# RELAY.net
KiCad netlist of a schematic drawn in Altium Designer
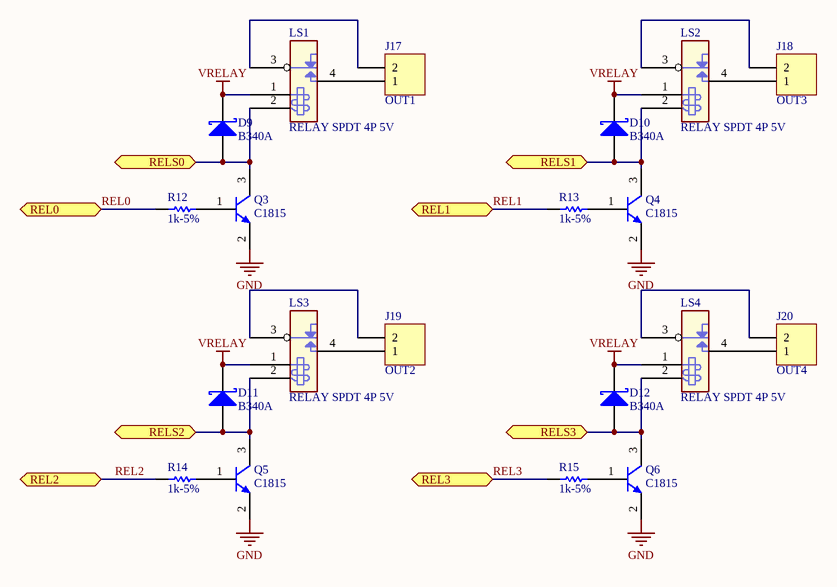
[diagram p0: RELAY.SchDoc]

(export (version "E")
  (design (tool "Eeschema 10.0.6"))
  (components
    (comp (ref "D9")
      (value "B340A")
      (footprint "DO_213AA")
      (description "DIODE SCHOTTKY 40V 3A SMA")
      (fields
        (field (name "DIGI-KEY PART NUMBER") "B340A-E3/61TGITR-ND")
        (field (name "MANUFACTURER PART NUMBER") "B340A-E3/61T")
        (field (name "PUBLISHER") "Altium Limited")
      )
      (libsource (lib "RobotClub") (part "D Schottky"))
    )
    (comp (ref "D10")
      (value "B340A")
      (footprint "DO_213AA")
      (description "DIODE SCHOTTKY 40V 3A SMA")
      (fields
        (field (name "DIGI-KEY PART NUMBER") "B340A-E3/61TGITR-ND")
        (field (name "MANUFACTURER PART NUMBER") "B340A-E3/61T")
        (field (name "PUBLISHER") "Altium Limited")
      )
      (libsource (lib "RobotClub") (part "D Schottky"))
    )
    (comp (ref "D11")
      (value "B340A")
      (footprint "DO_213AA")
      (description "DIODE SCHOTTKY 40V 3A SMA")
      (fields
        (field (name "DIGI-KEY PART NUMBER") "B340A-E3/61TGITR-ND")
        (field (name "MANUFACTURER PART NUMBER") "B340A-E3/61T")
        (field (name "PUBLISHER") "Altium Limited")
      )
      (libsource (lib "RobotClub") (part "D Schottky"))
    )
    (comp (ref "D12")
      (value "B340A")
      (footprint "DO_213AA")
      (description "DIODE SCHOTTKY 40V 3A SMA")
      (fields
        (field (name "DIGI-KEY PART NUMBER") "B340A-E3/61TGITR-ND")
        (field (name "MANUFACTURER PART NUMBER") "B340A-E3/61T")
        (field (name "PUBLISHER") "Altium Limited")
      )
      (libsource (lib "RobotClub") (part "D Schottky"))
    )
    (comp (ref "J17")
      (value "OUT1")
      (footprint "DOMINO NORMAL 2")
      (description "Header, 2-Pin")
      (fields (field (name "PUBLISHER") "Altium Limited"))
      (libsource (lib "RobotClub") (part "Header 2"))
    )
    (comp (ref "J18")
      (value "OUT3")
      (footprint "DOMINO NORMAL 2")
      (description "Header, 2-Pin")
      (fields (field (name "PUBLISHER") "Altium Limited"))
      (libsource (lib "RobotClub") (part "Header 2"))
    )
    (comp (ref "J19")
      (value "OUT2")
      (footprint "DOMINO NORMAL 2")
      (description "Header, 2-Pin")
      (fields (field (name "PUBLISHER") "Altium Limited"))
      (libsource (lib "RobotClub") (part "Header 2"))
    )
    (comp (ref "J20")
      (value "OUT4")
      (footprint "DOMINO NORMAL 2")
      (description "Header, 2-Pin")
      (fields (field (name "PUBLISHER") "Altium Limited"))
      (libsource (lib "RobotClub") (part "Header 2"))
    )
    (comp (ref "LS1")
      (value "RELAY SPDT 4P 5V")
      (footprint "RELAY_4PIN_5A_12")
      (libsource (lib "RobotClub") (part "RELAY SPDT 4P 5V"))
    )
    (comp (ref "LS2")
      (value "RELAY SPDT 4P 5V")
      (footprint "RELAY_4PIN_5A_12")
      (libsource (lib "RobotClub") (part "RELAY SPDT 4P 5V"))
    )
    (comp (ref "LS3")
      (value "RELAY SPDT 4P 5V")
      (footprint "RELAY_4PIN_5A_12")
      (libsource (lib "RobotClub") (part "RELAY SPDT 4P 5V"))
    )
    (comp (ref "LS4")
      (value "RELAY SPDT 4P 5V")
      (footprint "RELAY_4PIN_5A_12")
      (libsource (lib "RobotClub") (part "RELAY SPDT 4P 5V"))
    )
    (comp (ref "Q3")
      (value "C1815")
      (footprint "SOT-23B_N")
      (description "TRANSISTOR NPN 50V 150MA")
      (fields (field (name "DIGI-KEY PART NUMBER") "NA"))
      (libsource (lib "RobotClub") (part "NPN BEC"))
    )
    (comp (ref "Q4")
      (value "C1815")
      (footprint "SOT-23B_N")
      (description "TRANSISTOR NPN 50V 150MA")
      (fields (field (name "DIGI-KEY PART NUMBER") "NA"))
      (libsource (lib "RobotClub") (part "NPN BEC"))
    )
    (comp (ref "Q5")
      (value "C1815")
      (footprint "SOT-23B_N")
      (description "TRANSISTOR NPN 50V 150MA")
      (fields (field (name "DIGI-KEY PART NUMBER") "NA"))
      (libsource (lib "RobotClub") (part "NPN BEC"))
    )
    (comp (ref "Q6")
      (value "C1815")
      (footprint "SOT-23B_N")
      (description "TRANSISTOR NPN 50V 150MA")
      (fields (field (name "DIGI-KEY PART NUMBER") "NA"))
      (libsource (lib "RobotClub") (part "NPN BEC"))
    )
    (comp (ref "R12")
      (value "1k-5%")
      (footprint "R0603")
      (description "Resistor SMD 5%")
      (fields
        (field (name "DIGI-KEY PART NUMBER") "P3.24KLTR-ND")
        (field (name "MANUFACTURER") "Panasonic Electronic Components")
        (field (name "PUBLISHER") "Altium Limited")
      )
      (libsource (lib "RobotClub") (part "R_SMD5"))
    )
    (comp (ref "R13")
      (value "1k-5%")
      (footprint "R0603")
      (description "Resistor SMD 5%")
      (fields
        (field (name "DIGI-KEY PART NUMBER") "P3.24KLTR-ND")
        (field (name "MANUFACTURER") "Panasonic Electronic Components")
        (field (name "PUBLISHER") "Altium Limited")
      )
      (libsource (lib "RobotClub") (part "R_SMD5"))
    )
    (comp (ref "R14")
      (value "1k-5%")
      (footprint "R0603")
      (description "Resistor SMD 5%")
      (fields
        (field (name "DIGI-KEY PART NUMBER") "P3.24KLTR-ND")
        (field (name "MANUFACTURER") "Panasonic Electronic Components")
        (field (name "PUBLISHER") "Altium Limited")
      )
      (libsource (lib "RobotClub") (part "R_SMD5"))
    )
    (comp (ref "R15")
      (value "1k-5%")
      (footprint "R0603")
      (description "Resistor SMD 5%")
      (fields
        (field (name "DIGI-KEY PART NUMBER") "P3.24KLTR-ND")
        (field (name "MANUFACTURER") "Panasonic Electronic Components")
        (field (name "PUBLISHER") "Altium Limited")
      )
      (libsource (lib "RobotClub") (part "R_SMD5"))
    )
  )
  (nets
    (net (code "1") (name "/REL0") (class "Default")
      (node (ref "R12") (pin "1") (pinfunction "1_1") (pintype "passive"))
    )
    (net (code "2") (name "/REL1") (class "Default")
      (node (ref "R13") (pin "1") (pinfunction "1_1") (pintype "passive"))
    )
    (net (code "3") (name "/REL2") (class "Default")
      (node (ref "R14") (pin "1") (pinfunction "1_1") (pintype "passive"))
    )
    (net (code "4") (name "/REL3") (class "Default")
      (node (ref "R15") (pin "1") (pinfunction "1_1") (pintype "passive"))
    )
    (net (code "5") (name "/RELS0") (class "Default")
      (node (ref "D9") (pin "1") (pinfunction "A_1") (pintype "passive"))
      (node (ref "LS1") (pin "2") (pinfunction "COIL2_2") (pintype "passive"))
      (node (ref "Q3") (pin "3") (pinfunction "C_3") (pintype "passive"))
    )
    (net (code "6") (name "/RELS1") (class "Default")
      (node (ref "D10") (pin "1") (pinfunction "A_1") (pintype "passive"))
      (node (ref "LS2") (pin "2") (pinfunction "COIL2_2") (pintype "passive"))
      (node (ref "Q4") (pin "3") (pinfunction "C_3") (pintype "passive"))
    )
    (net (code "7") (name "/RELS2") (class "Default")
      (node (ref "D11") (pin "1") (pinfunction "A_1") (pintype "passive"))
      (node (ref "LS3") (pin "2") (pinfunction "COIL2_2") (pintype "passive"))
      (node (ref "Q5") (pin "3") (pinfunction "C_3") (pintype "passive"))
    )
    (net (code "8") (name "/RELS3") (class "Default")
      (node (ref "D12") (pin "1") (pinfunction "A_1") (pintype "passive"))
      (node (ref "LS4") (pin "2") (pinfunction "COIL2_2") (pintype "passive"))
      (node (ref "Q6") (pin "3") (pinfunction "C_3") (pintype "passive"))
    )
    (net (code "9") (name "GND") (class "Default")
      (node (ref "Q3") (pin "2") (pinfunction "E_2") (pintype "passive"))
      (node (ref "Q4") (pin "2") (pinfunction "E_2") (pintype "passive"))
      (node (ref "Q5") (pin "2") (pinfunction "E_2") (pintype "passive"))
      (node (ref "Q6") (pin "2") (pinfunction "E_2") (pintype "passive"))
    )
    (net (code "10") (name "Net-(LS1-COMMON)") (class "Default")
      (node (ref "J17") (pin "2") (pinfunction "2_2") (pintype "passive"))
      (node (ref "LS1") (pin "3") (pinfunction "COMMON_3") (pintype "passive"))
    )
    (net (code "11") (name "Net-(LS1-NO)") (class "Default")
      (node (ref "J17") (pin "1") (pinfunction "1_1") (pintype "passive"))
      (node (ref "LS1") (pin "4") (pinfunction "NO_4") (pintype "passive"))
    )
    (net (code "12") (name "Net-(LS2-COMMON)") (class "Default")
      (node (ref "J18") (pin "2") (pinfunction "2_2") (pintype "passive"))
      (node (ref "LS2") (pin "3") (pinfunction "COMMON_3") (pintype "passive"))
    )
    (net (code "13") (name "Net-(LS2-NO)") (class "Default")
      (node (ref "J18") (pin "1") (pinfunction "1_1") (pintype "passive"))
      (node (ref "LS2") (pin "4") (pinfunction "NO_4") (pintype "passive"))
    )
    (net (code "14") (name "Net-(LS3-COMMON)") (class "Default")
      (node (ref "J19") (pin "2") (pinfunction "2_2") (pintype "passive"))
      (node (ref "LS3") (pin "3") (pinfunction "COMMON_3") (pintype "passive"))
    )
    (net (code "15") (name "Net-(LS3-NO)") (class "Default")
      (node (ref "J19") (pin "1") (pinfunction "1_1") (pintype "passive"))
      (node (ref "LS3") (pin "4") (pinfunction "NO_4") (pintype "passive"))
    )
    (net (code "16") (name "Net-(LS4-COMMON)") (class "Default")
      (node (ref "J20") (pin "2") (pinfunction "2_2") (pintype "passive"))
      (node (ref "LS4") (pin "3") (pinfunction "COMMON_3") (pintype "passive"))
    )
    (net (code "17") (name "Net-(LS4-NO)") (class "Default")
      (node (ref "J20") (pin "1") (pinfunction "1_1") (pintype "passive"))
      (node (ref "LS4") (pin "4") (pinfunction "NO_4") (pintype "passive"))
    )
    (net (code "18") (name "Net-(Q3-B)") (class "Default")
      (node (ref "Q3") (pin "1") (pinfunction "B_1") (pintype "passive"))
      (node (ref "R12") (pin "2") (pinfunction "2_2") (pintype "passive"))
    )
    (net (code "19") (name "Net-(Q4-B)") (class "Default")
      (node (ref "Q4") (pin "1") (pinfunction "B_1") (pintype "passive"))
      (node (ref "R13") (pin "2") (pinfunction "2_2") (pintype "passive"))
    )
    (net (code "20") (name "Net-(Q5-B)") (class "Default")
      (node (ref "Q5") (pin "1") (pinfunction "B_1") (pintype "passive"))
      (node (ref "R14") (pin "2") (pinfunction "2_2") (pintype "passive"))
    )
    (net (code "21") (name "Net-(Q6-B)") (class "Default")
      (node (ref "Q6") (pin "1") (pinfunction "B_1") (pintype "passive"))
      (node (ref "R15") (pin "2") (pinfunction "2_2") (pintype "passive"))
    )
    (net (code "22") (name "VRELAY") (class "Default")
      (node (ref "D10") (pin "2") (pinfunction "K_2") (pintype "passive"))
      (node (ref "D11") (pin "2") (pinfunction "K_2") (pintype "passive"))
      (node (ref "D12") (pin "2") (pinfunction "K_2") (pintype "passive"))
      (node (ref "D9") (pin "2") (pinfunction "K_2") (pintype "passive"))
      (node (ref "LS1") (pin "1") (pinfunction "COIL1_1") (pintype "passive"))
      (node (ref "LS2") (pin "1") (pinfunction "COIL1_1") (pintype "passive"))
      (node (ref "LS3") (pin "1") (pinfunction "COIL1_1") (pintype "passive"))
      (node (ref "LS4") (pin "1") (pinfunction "COIL1_1") (pintype "passive"))
    )
  )
)
